# flap_controller_v2.net
KiCad netlist of a schematic drawn in EasyEDA Pro
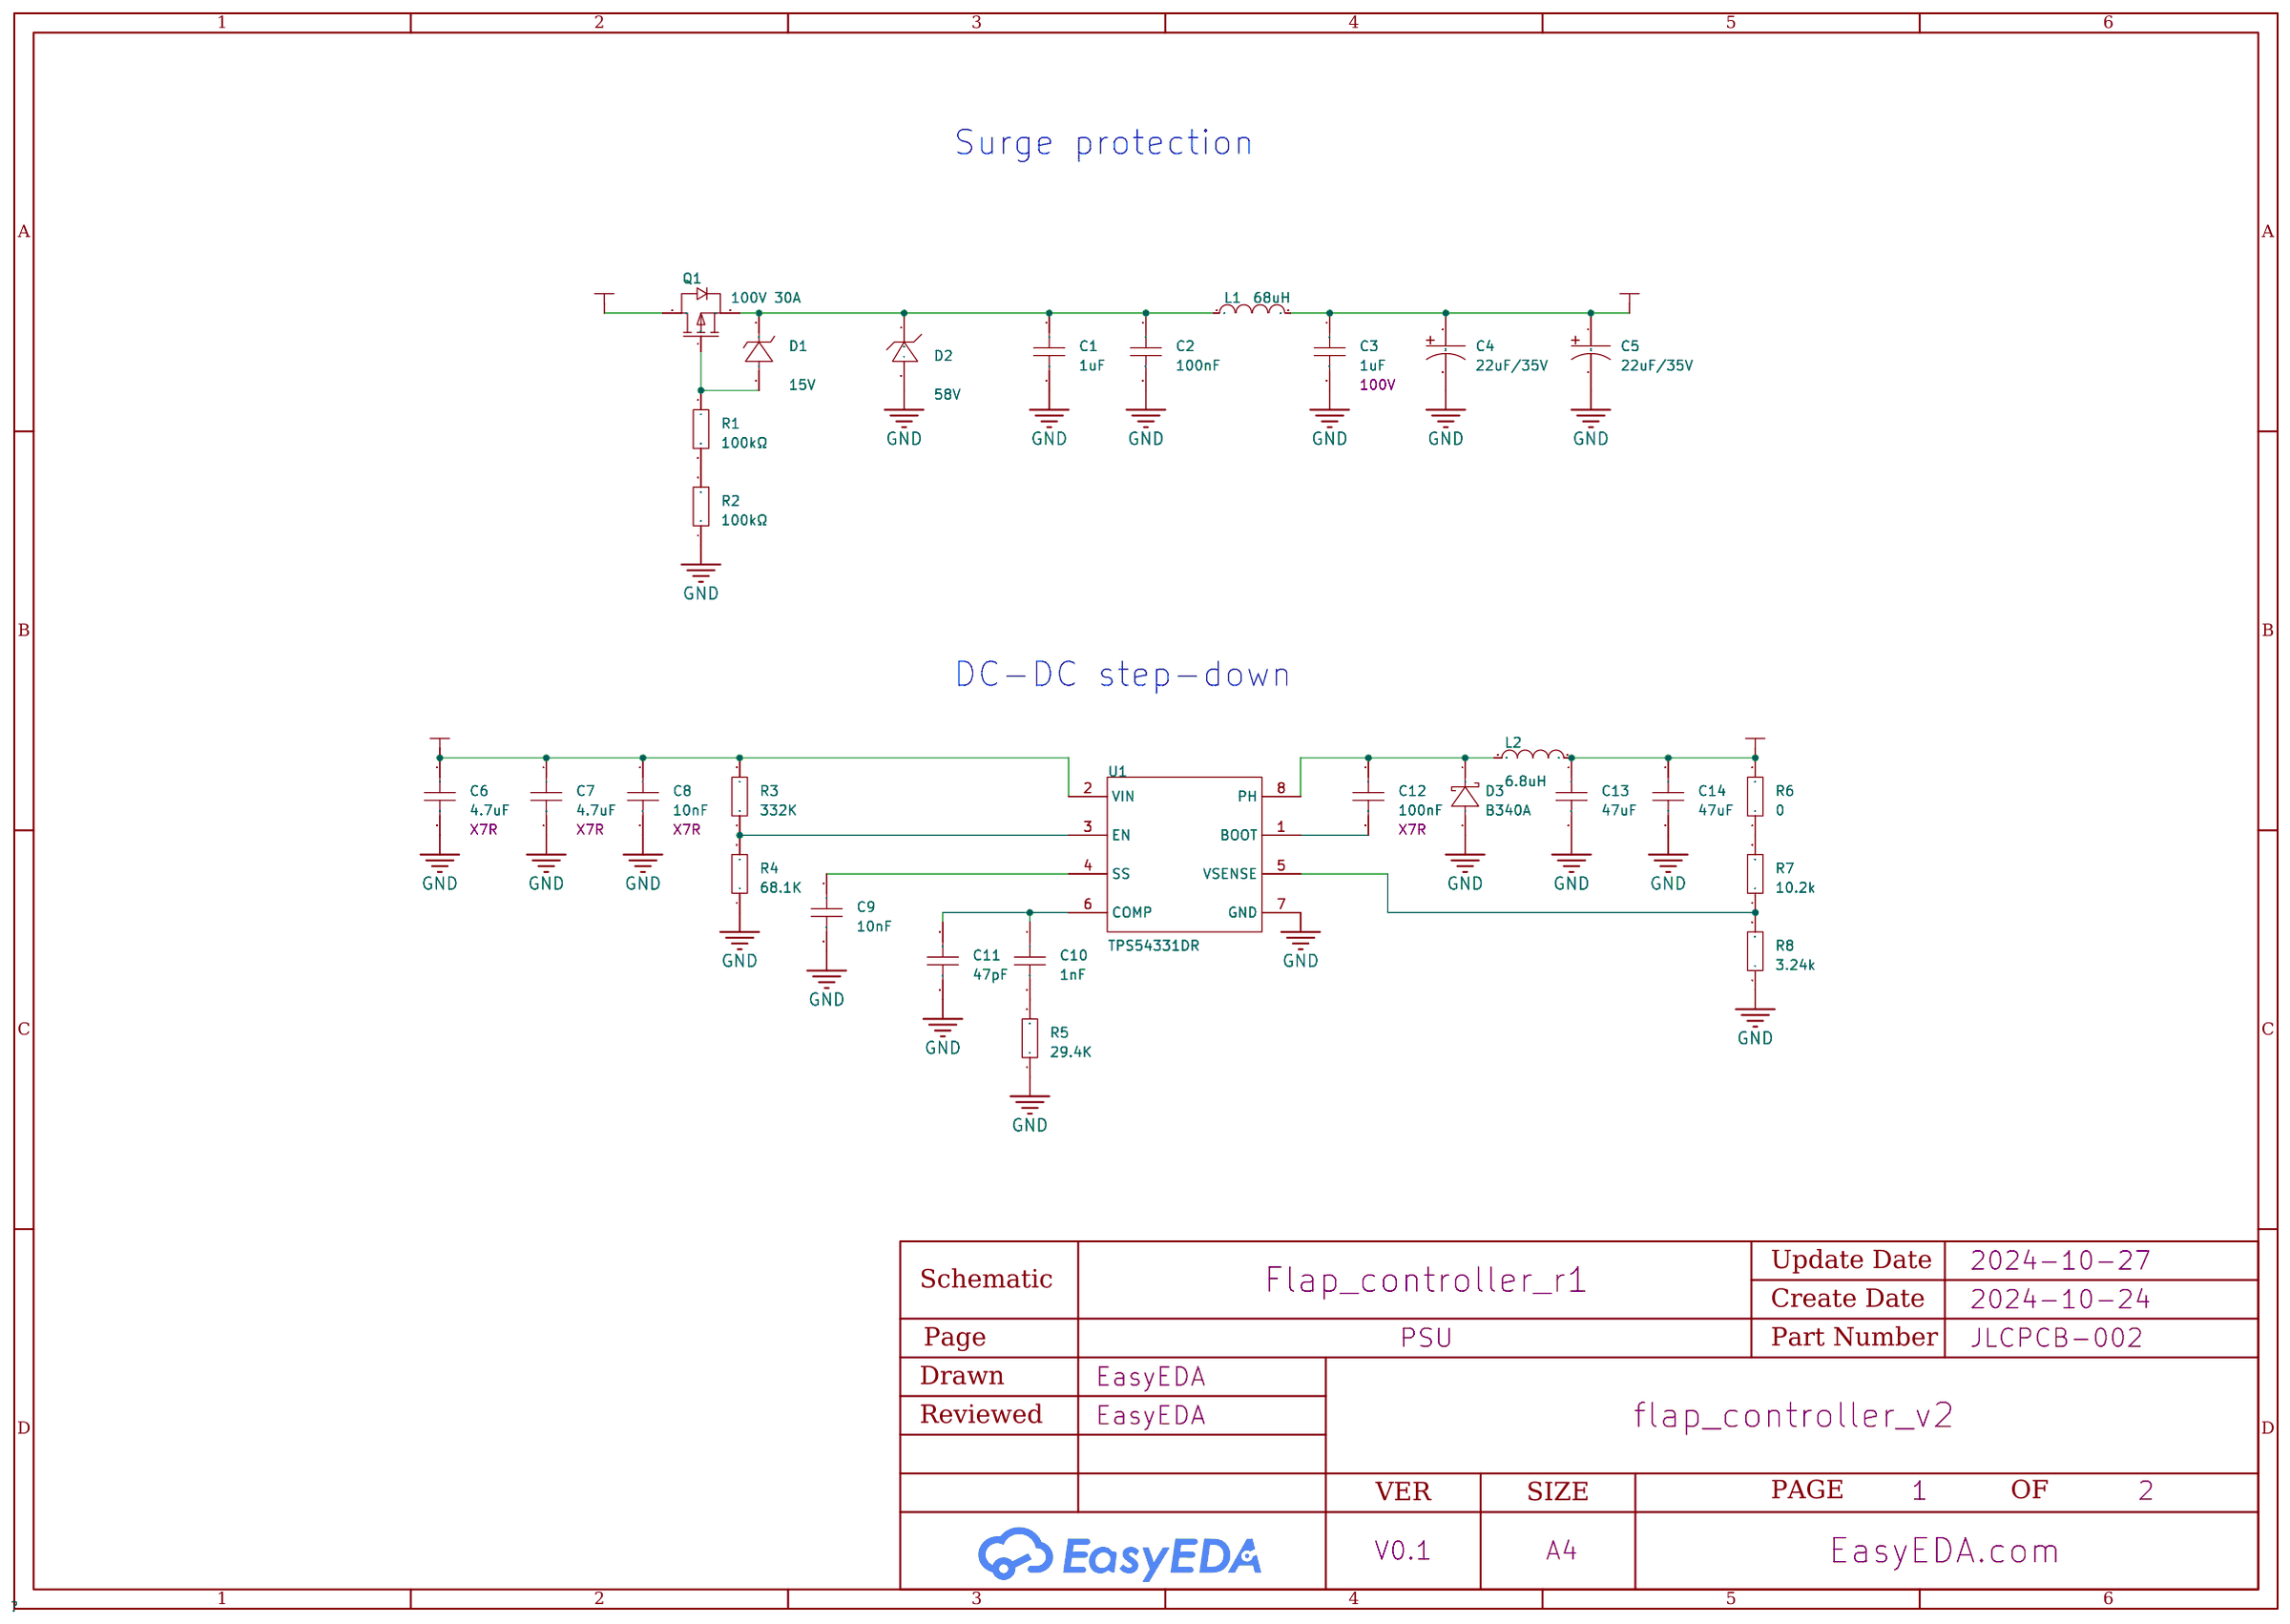
[diagram p0: PSU]
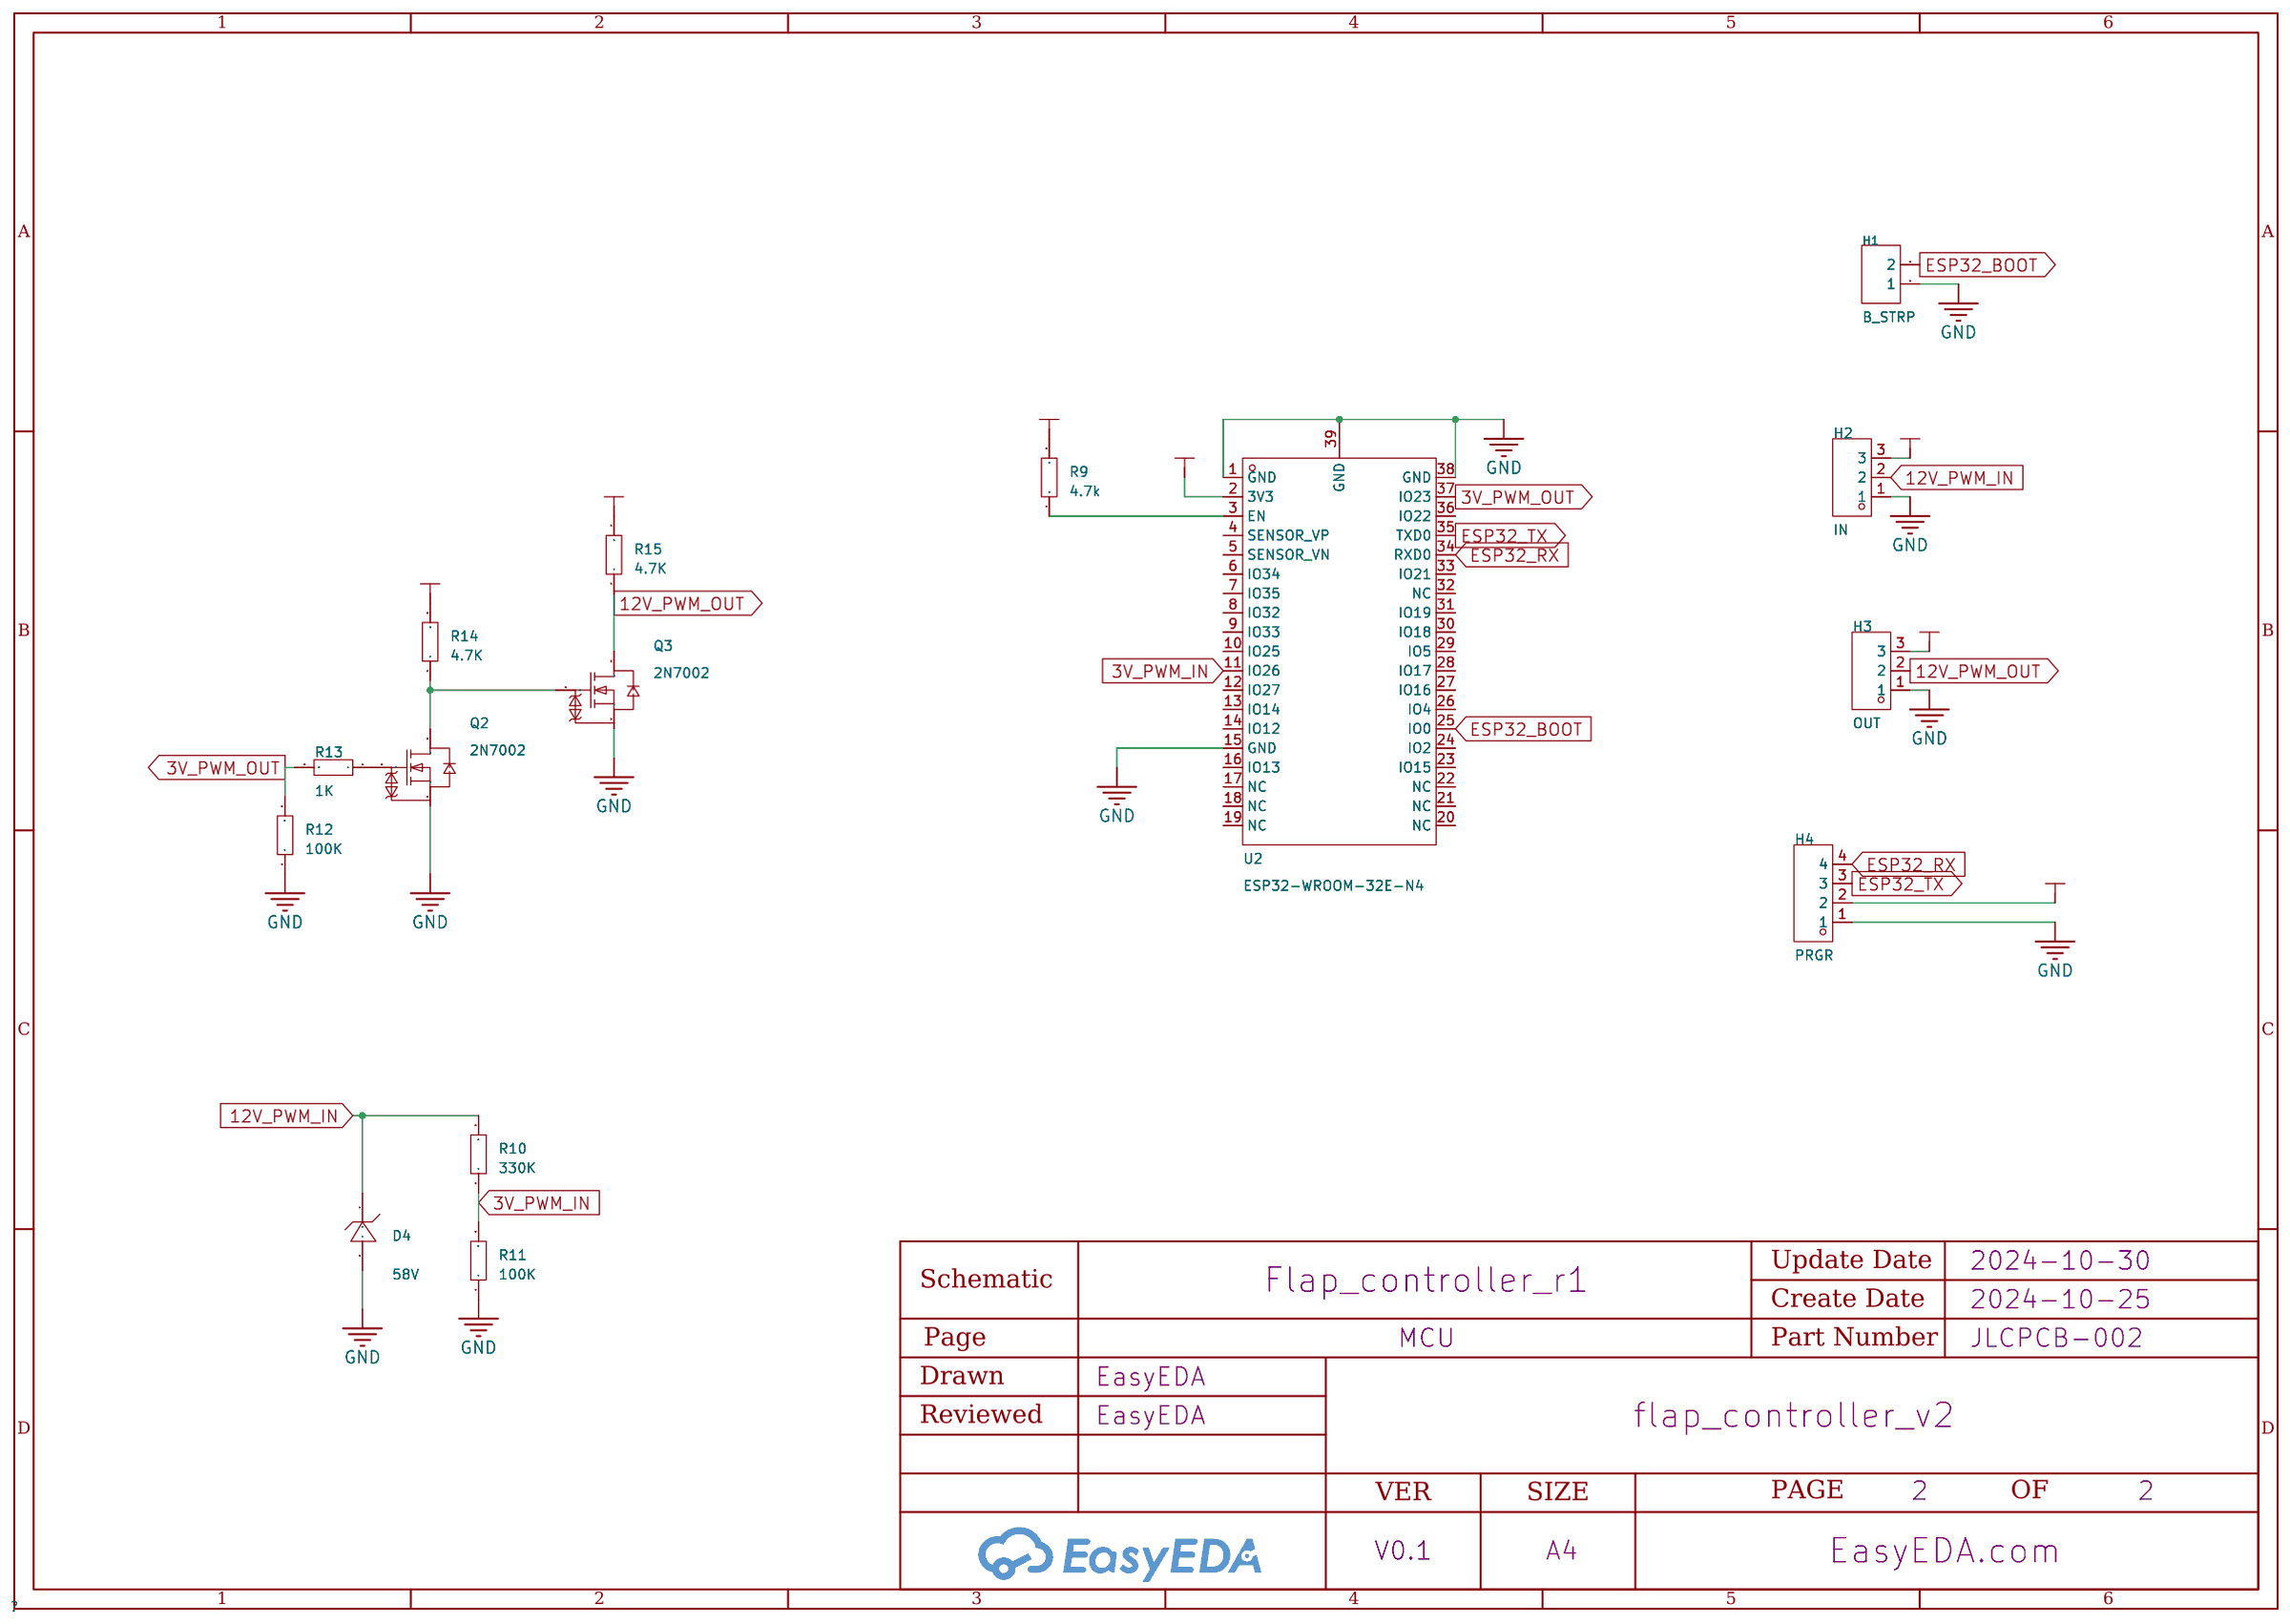
[diagram p1: MCU]

(export (version "E")
  (design (tool "Eeschema 10.0.6"))
  (components
    (comp (ref "C1")
      (value "1uF")
      (footprint "easyedapro:C0603")
      (fields (field (name "Manufacturer Part") "C0603X105K025T") (field (name "Manufacturer") "IHHEC(禾伸堂)"))
      (libsource (lib "easyedapro") (part "CAP"))
    )
    (comp (ref "C2")
      (value "100nF")
      (footprint "easyedapro:C0603")
      (fields (field (name "Manufacturer Part") "C0603X104K050T") (field (name "Manufacturer") "IHHEC(禾伸堂)"))
      (libsource (lib "easyedapro") (part "CAP"))
    )
    (comp (ref "C3")
      (value "1uF")
      (footprint "easyedapro:C0603")
      (fields (field (name "Voltage") "100V"))
      (libsource (lib "easyedapro") (part "CAP"))
    )
    (comp (ref "C4")
      (value "22uF/35V")
      (footprint "easyedapro:CAP-SMD_BD5.0-L5.3-W5.3-LS6.0-FD")
      (libsource (lib "easyedapro") (part "22UF/35V"))
    )
    (comp (ref "C5")
      (value "22uF/35V")
      (footprint "easyedapro:CAP-SMD_BD5.0-L5.3-W5.3-LS6.0-FD")
      (libsource (lib "easyedapro") (part "22UF/35V"))
    )
    (comp (ref "C6")
      (value "4.7uF")
      (footprint "easyedapro:C0603")
      (description "X7R")
      (libsource (lib "easyedapro") (part "CAP"))
    )
    (comp (ref "C7")
      (value "4.7uF")
      (footprint "easyedapro:C0603")
      (description "X7R")
      (libsource (lib "easyedapro") (part "CAP"))
    )
    (comp (ref "C8")
      (value "10nF")
      (footprint "easyedapro:C0603")
      (fields (field (name "Supplier Footprint") "X7R"))
      (libsource (lib "easyedapro") (part "CAP"))
    )
    (comp (ref "C9")
      (value "10nF")
      (footprint "easyedapro:C0603")
      (libsource (lib "easyedapro") (part "CAP"))
    )
    (comp (ref "C10")
      (value "1nF")
      (footprint "easyedapro:C0603")
      (libsource (lib "easyedapro") (part "CAP"))
    )
    (comp (ref "C11")
      (value "47pF")
      (footprint "easyedapro:C0603")
      (libsource (lib "easyedapro") (part "CAP"))
    )
    (comp (ref "C12")
      (value "100nF")
      (footprint "easyedapro:C0603")
      (description "X7R")
      (libsource (lib "easyedapro") (part "CAP"))
    )
    (comp (ref "C13")
      (value "47uF")
      (footprint "easyedapro:C0603")
      (libsource (lib "easyedapro") (part "CAP"))
    )
    (comp (ref "C14")
      (value "47uF")
      (footprint "easyedapro:C0603")
      (libsource (lib "easyedapro") (part "CAP"))
    )
    (comp (ref "D1")
      (value "15V")
      (footprint "easyedapro:SOD-323_L1.7-W1.3-LS2.5-RD")
      (fields (field (name "Manufacturer Part") "SOD-323"))
      (libsource (lib "easyedapro") (part "SOD-323_C9900016724"))
    )
    (comp (ref "D2")
      (value "58V")
      (footprint "easyedapro:SMB_L4.6-W3.6-LS5.3-RD")
      (fields (field (name "Manufacturer Part") "DO-214AA"))
      (libsource (lib "easyedapro") (part "DO-214AA"))
    )
    (comp (ref "D3")
      (value "B340A")
      (footprint "easyedapro:SMA_L4.3-W2.6-LS5.0-RD")
      (fields (field (name "Manufacturer") "FUXINSEMI(富芯森美)"))
      (libsource (lib "easyedapro") (part "B340A_C3018525"))
    )
    (comp (ref "L1")
      (value "68uH")
      (footprint "easyedapro:L0603")
      (fields (field (name "Manufacturer Part") "CY54-68UH") (field (name "Manufacturer") "SHOU HAN(首韩)"))
      (libsource (lib "easyedapro") (part "电感"))
    )
    (comp (ref "L2")
      (value "6.8uH")
      (footprint "easyedapro:IND-SMD_L4.5-W4.0")
      (fields (field (name "Manufacturer Part") "CY43-6.8UH") (field (name "Manufacturer") "SHOU HAN(首韩)"))
      (libsource (lib "easyedapro") (part "CY43-6.8UH"))
    )
    (comp (ref "Q1")
      (value "100V 30A")
      (footprint "easyedapro:TO-252-2_L6.6-W6.1-P4.57-LS10.1-BL")
      (fields (field (name "Manufacturer Part") "AP30P10D") (field (name "Manufacturer") "APM(永源微电子)"))
      (libsource (lib "easyedapro") (part "AP30P10D"))
    )
    (comp (ref "R1")
      (value "100kΩ")
      (footprint "easyedapro:R0603")
      (fields (field (name "Manufacturer Part") "SCR0603F100K") (field (name "Manufacturer") "VO(翔胜)"))
      (libsource (lib "easyedapro") (part "Res"))
    )
    (comp (ref "R2")
      (value "100kΩ")
      (footprint "easyedapro:R0603")
      (fields (field (name "Manufacturer Part") "SCR0603F100K") (field (name "Manufacturer") "VO(翔胜)"))
      (libsource (lib "easyedapro") (part "Res"))
    )
    (comp (ref "R3")
      (value "332K")
      (footprint "easyedapro:R0603")
      (libsource (lib "easyedapro") (part "Res"))
    )
    (comp (ref "R4")
      (value "68.1K")
      (footprint "easyedapro:R0603")
      (libsource (lib "easyedapro") (part "Res"))
    )
    (comp (ref "R5")
      (value "29.4K")
      (footprint "easyedapro:R0603")
      (libsource (lib "easyedapro") (part "Res"))
    )
    (comp (ref "R6") (value "0") (footprint "easyedapro:R0603") (libsource (lib "easyedapro") (part "Res")))
    (comp (ref "R7")
      (value "10.2k")
      (footprint "easyedapro:R0603")
      (libsource (lib "easyedapro") (part "Res"))
    )
    (comp (ref "R8")
      (value "3.24k")
      (footprint "easyedapro:R0603")
      (libsource (lib "easyedapro") (part "Res"))
    )
    (comp (ref "U1")
      (value "TPS54331DR")
      (footprint "easyedapro:SOIC-8_L5.0-W4.0-P1.27-LS6.0-BL")
      (fields (field (name "Manufacturer") "TI(德州仪器)"))
      (libsource (lib "easyedapro") (part "TPS54331DR"))
    )
    (comp (ref "D4")
      (value "58V")
      (footprint "easyedapro:SMB_L4.6-W3.6-LS5.3-RD")
      (fields (field (name "Manufacturer Part") "DO-214AA"))
      (libsource (lib "easyedapro") (part "DO-214AA"))
    )
    (comp (ref "H1")
      (value "B_STRP")
      (footprint "easyedapro:HDR-TH_2P-P2.54-V-F")
      (fields (field (name "Manufacturer Part") "B-2100S02P-A110") (field (name "Manufacturer") "Ckmtw(灿科盟)"))
      (libsource (lib "easyedapro") (part "Header-Female-2.54_1x2"))
    )
    (comp (ref "H2")
      (value "IN")
      (footprint "easyedapro:HDR-TH_3P-P2.00-V-M")
      (fields (field (name "Manufacturer Part") "3pin插件排针"))
      (libsource (lib "easyedapro") (part "3PIN插件排针"))
    )
    (comp (ref "H3")
      (value "OUT")
      (footprint "easyedapro:HDR-TH_3P-P2.00-V-M")
      (fields (field (name "Manufacturer Part") "3pin插件排针"))
      (libsource (lib "easyedapro") (part "3PIN插件排针"))
    )
    (comp (ref "H4")
      (value "PRGR")
      (footprint "easyedapro:HDR-TH_4P-P2.54-V-M")
      (fields (field (name "Manufacturer Part") "HDR2.54-LI-2x4P"))
      (libsource (lib "easyedapro") (part "HDR2.54-LI-2X4P"))
    )
    (comp (ref "Q2")
      (value "2N7002")
      (footprint "easyedapro:SOT-23-3_L3.0-W1.7-P0.95-LS2.9-BR")
      (fields (field (name "Manufacturer") "FOSAN(富信)"))
      (libsource (lib "easyedapro") (part "L2N7002SLLT1G"))
    )
    (comp (ref "Q3")
      (value "2N7002")
      (footprint "easyedapro:SOT-23-3_L3.0-W1.7-P0.95-LS2.9-BR")
      (fields (field (name "Manufacturer") "FOSAN(富信)"))
      (libsource (lib "easyedapro") (part "L2N7002SLLT1G"))
    )
    (comp (ref "R9")
      (value "4.7k")
      (footprint "easyedapro:R0603")
      (libsource (lib "easyedapro") (part "Res"))
    )
    (comp (ref "R10")
      (value "330K")
      (footprint "easyedapro:R0603")
      (libsource (lib "easyedapro") (part "Res"))
    )
    (comp (ref "R11")
      (value "100K")
      (footprint "easyedapro:R0603")
      (libsource (lib "easyedapro") (part "Res"))
    )
    (comp (ref "R12")
      (value "100K")
      (footprint "easyedapro:R0603")
      (libsource (lib "easyedapro") (part "Res"))
    )
    (comp (ref "R13") (value "1K") (footprint "easyedapro:R0603") (libsource (lib "easyedapro") (part "Res")))
    (comp (ref "R14")
      (value "4.7K")
      (footprint "easyedapro:R0603")
      (libsource (lib "easyedapro") (part "Res"))
    )
    (comp (ref "R15")
      (value "4.7K")
      (footprint "easyedapro:R0603")
      (libsource (lib "easyedapro") (part "Res"))
    )
    (comp (ref "U2")
      (value "ESP32-WROOM-32E-N4")
      (footprint "easyedapro:WIFI-SMD_ESP32-WROOM-32E")
      (fields (field (name "Manufacturer") "ESPRESSIF(乐鑫)"))
      (libsource (lib "easyedapro") (part "ESP32-WROOM-32E(4MB)"))
    )
  )
  (nets
    (net (code "1") (name "3V3") (class "Default")
      (node (ref "C13") (pin "1") (pinfunction "1_1") (pintype "input"))
      (node (ref "C14") (pin "1") (pinfunction "1_1") (pintype "input"))
      (node (ref "H4") (pin "2") (pinfunction "2_2") (pintype "unspecified"))
      (node (ref "L2") (pin "2") (pinfunction "2_2") (pintype "unspecified"))
      (node (ref "R6") (pin "2") (pinfunction "2_2") (pintype "input"))
      (node (ref "R9") (pin "2") (pinfunction "2_2") (pintype "input"))
      (node (ref "U2") (pin "2") (pinfunction "3V3_2") (pintype "unspecified"))
    )
    (net (code "2") (name "3V_PWM_IN") (class "Default")
      (node (ref "R10") (pin "1") (pinfunction "1_1") (pintype "input"))
      (node (ref "R11") (pin "2") (pinfunction "2_2") (pintype "input"))
      (node (ref "U2") (pin "11") (pinfunction "IO26_11") (pintype "unspecified"))
    )
    (net (code "3") (name "3V_PWM_OUT") (class "Default")
      (node (ref "R12") (pin "2") (pinfunction "2_2") (pintype "input"))
      (node (ref "R13") (pin "2") (pinfunction "2_2") (pintype "input"))
      (node (ref "U2") (pin "37") (pinfunction "IO23_37") (pintype "unspecified"))
    )
    (net (code "4") (name "12V") (class "Default")
      (node (ref "H2") (pin "3") (pinfunction "3_3") (pintype "unspecified"))
      (node (ref "H3") (pin "3") (pinfunction "3_3") (pintype "unspecified"))
      (node (ref "Q1") (pin "3") (pinfunction "D_3") (pintype "unspecified"))
    )
    (net (code "5") (name "12V_PWM_IN") (class "Default")
      (node (ref "D4") (pin "1") (pinfunction "C_1") (pintype "unspecified"))
      (node (ref "H2") (pin "2") (pinfunction "2_2") (pintype "unspecified"))
      (node (ref "R10") (pin "2") (pinfunction "2_2") (pintype "input"))
    )
    (net (code "6") (name "12V_PWM_OUT") (class "Default")
      (node (ref "H3") (pin "2") (pinfunction "2_2") (pintype "unspecified"))
      (node (ref "Q3") (pin "3") (pinfunction "D_3") (pintype "unspecified"))
      (node (ref "R15") (pin "1") (pinfunction "1_1") (pintype "input"))
    )
    (net (code "7") (name "12V_S") (class "Default")
      (node (ref "C3") (pin "1") (pinfunction "1_1") (pintype "input"))
      (node (ref "C4") (pin "1") (pinfunction "1_1") (pintype "unspecified"))
      (node (ref "C5") (pin "1") (pinfunction "1_1") (pintype "unspecified"))
      (node (ref "C6") (pin "1") (pinfunction "1_1") (pintype "input"))
      (node (ref "C7") (pin "1") (pinfunction "1_1") (pintype "input"))
      (node (ref "C8") (pin "1") (pinfunction "1_1") (pintype "input"))
      (node (ref "L1") (pin "2") (pinfunction "2_2") (pintype "input"))
      (node (ref "R14") (pin "2") (pinfunction "2_2") (pintype "input"))
      (node (ref "R15") (pin "2") (pinfunction "2_2") (pintype "input"))
      (node (ref "R3") (pin "2") (pinfunction "2_2") (pintype "input"))
      (node (ref "U1") (pin "2") (pinfunction "VIN_2") (pintype "unspecified"))
    )
    (net (code "8") (name "ESP32_BOOT") (class "Default")
      (node (ref "H1") (pin "2") (pinfunction "2_2") (pintype "input"))
      (node (ref "U2") (pin "25") (pinfunction "IO0_25") (pintype "unspecified"))
    )
    (net (code "9") (name "ESP32_RX") (class "Default")
      (node (ref "H4") (pin "4") (pinfunction "4_4") (pintype "unspecified"))
      (node (ref "U2") (pin "34") (pinfunction "RXD0_34") (pintype "unspecified"))
    )
    (net (code "10") (name "ESP32_TX") (class "Default")
      (node (ref "H4") (pin "3") (pinfunction "3_3") (pintype "unspecified"))
      (node (ref "U2") (pin "35") (pinfunction "TXD0_35") (pintype "unspecified"))
    )
    (net (code "11") (name "GND") (class "Default")
      (node (ref "C1") (pin "2") (pinfunction "2_2") (pintype "input"))
      (node (ref "C11") (pin "2") (pinfunction "2_2") (pintype "input"))
      (node (ref "C13") (pin "2") (pinfunction "2_2") (pintype "input"))
      (node (ref "C14") (pin "2") (pinfunction "2_2") (pintype "input"))
      (node (ref "C2") (pin "2") (pinfunction "2_2") (pintype "input"))
      (node (ref "C3") (pin "2") (pinfunction "2_2") (pintype "input"))
      (node (ref "C4") (pin "2") (pinfunction "2_2") (pintype "unspecified"))
      (node (ref "C5") (pin "2") (pinfunction "2_2") (pintype "unspecified"))
      (node (ref "C6") (pin "2") (pinfunction "2_2") (pintype "input"))
      (node (ref "C7") (pin "2") (pinfunction "2_2") (pintype "input"))
      (node (ref "C8") (pin "2") (pinfunction "2_2") (pintype "input"))
      (node (ref "C9") (pin "2") (pinfunction "2_2") (pintype "input"))
      (node (ref "D2") (pin "2") (pinfunction "A_2") (pintype "unspecified"))
      (node (ref "D3") (pin "2") (pinfunction "A_2") (pintype "unspecified"))
      (node (ref "D4") (pin "2") (pinfunction "A_2") (pintype "unspecified"))
      (node (ref "H1") (pin "1") (pinfunction "1_1") (pintype "input"))
      (node (ref "H2") (pin "1") (pinfunction "1_1") (pintype "unspecified"))
      (node (ref "H3") (pin "1") (pinfunction "1_1") (pintype "unspecified"))
      (node (ref "H4") (pin "1") (pinfunction "1_1") (pintype "unspecified"))
      (node (ref "Q2") (pin "2") (pinfunction "S_2") (pintype "unspecified"))
      (node (ref "Q3") (pin "2") (pinfunction "S_2") (pintype "unspecified"))
      (node (ref "R11") (pin "1") (pinfunction "1_1") (pintype "input"))
      (node (ref "R12") (pin "1") (pinfunction "1_1") (pintype "input"))
      (node (ref "R2") (pin "1") (pinfunction "1_1") (pintype "input"))
      (node (ref "R4") (pin "1") (pinfunction "1_1") (pintype "input"))
      (node (ref "R5") (pin "1") (pinfunction "1_1") (pintype "input"))
      (node (ref "R8") (pin "1") (pinfunction "1_1") (pintype "input"))
      (node (ref "U1") (pin "7") (pinfunction "GND_7") (pintype "unspecified"))
      (node (ref "U2") (pin "1") (pinfunction "GND_1") (pintype "unspecified"))
      (node (ref "U2") (pin "15") (pinfunction "GND_15") (pintype "unspecified"))
      (node (ref "U2") (pin "38") (pinfunction "GND_38") (pintype "unspecified"))
      (node (ref "U2") (pin "39") (pinfunction "GND_39") (pintype "unspecified"))
    )
    (net (code "12") (name "Net-(C10-Pad2)") (class "Default")
      (node (ref "C10") (pin "2") (pinfunction "2_2") (pintype "input"))
      (node (ref "R5") (pin "2") (pinfunction "2_2") (pintype "input"))
    )
    (net (code "13") (name "Net-(D1-A)") (class "Default")
      (node (ref "D1") (pin "2") (pinfunction "A_2") (pintype "unspecified"))
      (node (ref "Q1") (pin "1") (pinfunction "G_1") (pintype "unspecified"))
      (node (ref "R1") (pin "1") (pinfunction "1_1") (pintype "input"))
    )
    (net (code "14") (name "Net-(D1-K)") (class "Default")
      (node (ref "C1") (pin "1") (pinfunction "1_1") (pintype "input"))
      (node (ref "C2") (pin "1") (pinfunction "1_1") (pintype "input"))
      (node (ref "D1") (pin "1") (pinfunction "K_1") (pintype "unspecified"))
      (node (ref "D2") (pin "1") (pinfunction "C_1") (pintype "unspecified"))
      (node (ref "L1") (pin "1") (pinfunction "1_1") (pintype "input"))
      (node (ref "Q1") (pin "2") (pinfunction "S_2") (pintype "unspecified"))
    )
    (net (code "15") (name "Net-(D3-K)") (class "Default")
      (node (ref "C12") (pin "1") (pinfunction "1_1") (pintype "input"))
      (node (ref "D3") (pin "1") (pinfunction "K_1") (pintype "unspecified"))
      (node (ref "L2") (pin "1") (pinfunction "1_1") (pintype "unspecified"))
      (node (ref "U1") (pin "8") (pinfunction "PH_8") (pintype "unspecified"))
    )
    (net (code "16") (name "Net-(Q2-D)") (class "Default")
      (node (ref "Q2") (pin "3") (pinfunction "D_3") (pintype "unspecified"))
      (node (ref "Q3") (pin "1") (pinfunction "G_1") (pintype "unspecified"))
      (node (ref "R14") (pin "1") (pinfunction "1_1") (pintype "input"))
    )
    (net (code "17") (name "Net-(Q2-G)") (class "Default")
      (node (ref "Q2") (pin "1") (pinfunction "G_1") (pintype "unspecified"))
      (node (ref "R13") (pin "1") (pinfunction "1_1") (pintype "input"))
    )
    (net (code "18") (name "Net-(R1-Pad2)") (class "Default")
      (node (ref "R1") (pin "2") (pinfunction "2_2") (pintype "input"))
      (node (ref "R2") (pin "2") (pinfunction "2_2") (pintype "input"))
    )
    (net (code "19") (name "Net-(R6-Pad1)") (class "Default")
      (node (ref "R6") (pin "1") (pinfunction "1_1") (pintype "input"))
      (node (ref "R7") (pin "2") (pinfunction "2_2") (pintype "input"))
    )
    (net (code "20") (name "Net-(U1-BOOT)") (class "Default")
      (node (ref "C12") (pin "2") (pinfunction "2_2") (pintype "input"))
      (node (ref "U1") (pin "1") (pinfunction "BOOT_1") (pintype "unspecified"))
    )
    (net (code "21") (name "Net-(U1-COMP)") (class "Default")
      (node (ref "C10") (pin "1") (pinfunction "1_1") (pintype "input"))
      (node (ref "C11") (pin "1") (pinfunction "1_1") (pintype "input"))
      (node (ref "U1") (pin "6") (pinfunction "COMP_6") (pintype "unspecified"))
    )
    (net (code "22") (name "Net-(U1-EN)") (class "Default")
      (node (ref "R3") (pin "1") (pinfunction "1_1") (pintype "input"))
      (node (ref "R4") (pin "2") (pinfunction "2_2") (pintype "input"))
      (node (ref "U1") (pin "3") (pinfunction "EN_3") (pintype "unspecified"))
    )
    (net (code "23") (name "Net-(U1-SS)") (class "Default")
      (node (ref "C9") (pin "1") (pinfunction "1_1") (pintype "input"))
      (node (ref "U1") (pin "4") (pinfunction "SS_4") (pintype "unspecified"))
    )
    (net (code "24") (name "Net-(U1-VSENSE)") (class "Default")
      (node (ref "R7") (pin "1") (pinfunction "1_1") (pintype "input"))
      (node (ref "R8") (pin "2") (pinfunction "2_2") (pintype "input"))
      (node (ref "U1") (pin "5") (pinfunction "VSENSE_5") (pintype "unspecified"))
    )
    (net (code "25") (name "Net-(U2-EN)") (class "Default")
      (node (ref "R9") (pin "1") (pinfunction "1_1") (pintype "input"))
      (node (ref "U2") (pin "3") (pinfunction "EN_3") (pintype "unspecified"))
    )
    (net (code "26") (name "unconnected-(U2-IO2-Pad24)") (class "Default")
      (node (ref "U2") (pin "24") (pinfunction "IO2_24") (pintype "unspecified"))
    )
    (net (code "27") (name "unconnected-(U2-IO4-Pad26)") (class "Default")
      (node (ref "U2") (pin "26") (pinfunction "IO4_26") (pintype "unspecified"))
    )
    (net (code "28") (name "unconnected-(U2-IO5-Pad29)") (class "Default")
      (node (ref "U2") (pin "29") (pinfunction "IO5_29") (pintype "unspecified"))
    )
    (net (code "29") (name "unconnected-(U2-IO12-Pad14)") (class "Default")
      (node (ref "U2") (pin "14") (pinfunction "IO12_14") (pintype "unspecified"))
    )
    (net (code "30") (name "unconnected-(U2-IO13-Pad16)") (class "Default")
      (node (ref "U2") (pin "16") (pinfunction "IO13_16") (pintype "unspecified"))
    )
    (net (code "31") (name "unconnected-(U2-IO14-Pad13)") (class "Default")
      (node (ref "U2") (pin "13") (pinfunction "IO14_13") (pintype "unspecified"))
    )
    (net (code "32") (name "unconnected-(U2-IO15-Pad23)") (class "Default")
      (node (ref "U2") (pin "23") (pinfunction "IO15_23") (pintype "unspecified"))
    )
    (net (code "33") (name "unconnected-(U2-IO16-Pad27)") (class "Default")
      (node (ref "U2") (pin "27") (pinfunction "IO16_27") (pintype "unspecified"))
    )
    (net (code "34") (name "unconnected-(U2-IO17-Pad28)") (class "Default")
      (node (ref "U2") (pin "28") (pinfunction "IO17_28") (pintype "unspecified"))
    )
    (net (code "35") (name "unconnected-(U2-IO18-Pad30)") (class "Default")
      (node (ref "U2") (pin "30") (pinfunction "IO18_30") (pintype "unspecified"))
    )
    (net (code "36") (name "unconnected-(U2-IO19-Pad31)") (class "Default")
      (node (ref "U2") (pin "31") (pinfunction "IO19_31") (pintype "unspecified"))
    )
    (net (code "37") (name "unconnected-(U2-IO21-Pad33)") (class "Default")
      (node (ref "U2") (pin "33") (pinfunction "IO21_33") (pintype "unspecified"))
    )
    (net (code "38") (name "unconnected-(U2-IO22-Pad36)") (class "Default")
      (node (ref "U2") (pin "36") (pinfunction "IO22_36") (pintype "unspecified"))
    )
    (net (code "39") (name "unconnected-(U2-IO25-Pad10)") (class "Default")
      (node (ref "U2") (pin "10") (pinfunction "IO25_10") (pintype "unspecified"))
    )
    (net (code "40") (name "unconnected-(U2-IO27-Pad12)") (class "Default")
      (node (ref "U2") (pin "12") (pinfunction "IO27_12") (pintype "unspecified"))
    )
    (net (code "41") (name "unconnected-(U2-IO32-Pad8)") (class "Default")
      (node (ref "U2") (pin "8") (pinfunction "IO32_8") (pintype "unspecified"))
    )
    (net (code "42") (name "unconnected-(U2-IO33-Pad9)") (class "Default")
      (node (ref "U2") (pin "9") (pinfunction "IO33_9") (pintype "unspecified"))
    )
    (net (code "43") (name "unconnected-(U2-IO34-Pad6)") (class "Default")
      (node (ref "U2") (pin "6") (pinfunction "IO34_6") (pintype "unspecified"))
    )
    (net (code "44") (name "unconnected-(U2-IO35-Pad7)") (class "Default")
      (node (ref "U2") (pin "7") (pinfunction "IO35_7") (pintype "unspecified"))
    )
    (net (code "45") (name "unconnected-(U2-NC-Pad17)") (class "Default")
      (node (ref "U2") (pin "17") (pinfunction "NC_17") (pintype "unspecified"))
    )
    (net (code "46") (name "unconnected-(U2-NC-Pad18)") (class "Default")
      (node (ref "U2") (pin "18") (pinfunction "NC_18") (pintype "unspecified"))
    )
    (net (code "47") (name "unconnected-(U2-NC-Pad19)") (class "Default")
      (node (ref "U2") (pin "19") (pinfunction "NC_19") (pintype "unspecified"))
    )
    (net (code "48") (name "unconnected-(U2-NC-Pad20)") (class "Default")
      (node (ref "U2") (pin "20") (pinfunction "NC_20") (pintype "unspecified"))
    )
    (net (code "49") (name "unconnected-(U2-NC-Pad21)") (class "Default")
      (node (ref "U2") (pin "21") (pinfunction "NC_21") (pintype "unspecified"))
    )
    (net (code "50") (name "unconnected-(U2-NC-Pad22)") (class "Default")
      (node (ref "U2") (pin "22") (pinfunction "NC_22") (pintype "unspecified"))
    )
    (net (code "51") (name "unconnected-(U2-NC-Pad32)") (class "Default")
      (node (ref "U2") (pin "32") (pinfunction "NC_32") (pintype "unspecified"))
    )
    (net (code "52") (name "unconnected-(U2-SENSOR_VN-Pad5)") (class "Default")
      (node (ref "U2") (pin "5") (pinfunction "SENSOR_VN_5") (pintype "unspecified"))
    )
    (net (code "53") (name "unconnected-(U2-SENSOR_VP-Pad4)") (class "Default")
      (node (ref "U2") (pin "4") (pinfunction "SENSOR_VP_4") (pintype "unspecified"))
    )
  )
)
